# MQ303A_EEPROM_v3_0_-_para_testes.net
KiCad netlist of a schematic drawn in EAGLE
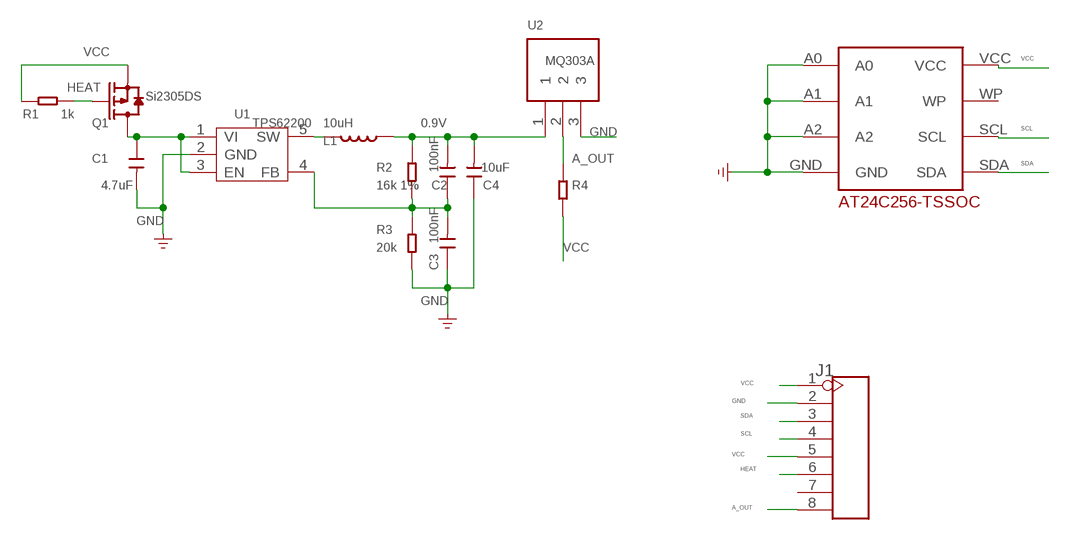
[diagram p0: schematic, sheet 1]

(export (version "E")
  (design (tool "Eeschema 10.0.6"))
  (components
    (comp (ref "C1")
      (value "4.7uF")
      (footprint "eagle-import:C0805")
      (libsource (lib "eagle-import") (part "C-0805"))
    )
    (comp (ref "C2")
      (value "100nF")
      (footprint "eagle-import:C0603")
      (libsource (lib "eagle-import") (part "C-0603"))
    )
    (comp (ref "C3")
      (value "100nF")
      (footprint "eagle-import:C0603")
      (libsource (lib "eagle-import") (part "C-0603"))
    )
    (comp (ref "C4")
      (value "10uF")
      (footprint "eagle-import:C0805")
      (libsource (lib "eagle-import") (part "C-0805"))
    )
    (comp (ref "J1")
      (value "HEADER-8P-2.54")
      (footprint "eagle-import:8P-2.54")
      (libsource (lib "eagle-import") (part "HEADER-8P-2.54"))
    )
    (comp (ref "L1")
      (value "10uH")
      (footprint "eagle-import:PIO73")
      (libsource (lib "eagle-import") (part "L'PIO73'"))
    )
    (comp (ref "Q1")
      (value "Si2305DS")
      (footprint "eagle-import:SOT23")
      (libsource (lib "eagle-import") (part "MOSFET-P'SI2323CDS/SI2305DS{lt}BR{gt}'"))
    )
    (comp (ref "R1")
      (value "1k")
      (footprint "eagle-import:R0603")
      (libsource (lib "eagle-import") (part "R-0603"))
    )
    (comp (ref "R2")
      (value "16k 1%")
      (footprint "eagle-import:R0603")
      (libsource (lib "eagle-import") (part "R-0603"))
    )
    (comp (ref "R3")
      (value "20k")
      (footprint "eagle-import:R0603")
      (libsource (lib "eagle-import") (part "R-0603"))
    )
    (comp (ref "R4")
      (value "R-0603")
      (footprint "eagle-import:R0603")
      (libsource (lib "eagle-import") (part "R-0603"))
    )
    (comp (ref "U$1")
      (value "DECADE-AT24C256-10TI-2.7")
      (footprint "eagle-import:DECADE-AT24CXX")
      (libsource (lib "eagle-import") (part "DECADE-AT24C256-10TI-2.7"))
    )
    (comp (ref "U1")
      (value "TPS62200")
      (footprint "eagle-import:SOT23-5")
      (libsource (lib "eagle-import") (part "TPS62200DBV"))
    )
    (comp (ref "U2")
      (value "MQ303A")
      (footprint "eagle-import:MQ303A")
      (libsource (lib "eagle-import") (part "MQ303A"))
    )
  )
  (nets
    (net (code "1") (name "/0.9V") (class "Default")
      (node (ref "C2") (pin "2") (pinfunction "2_2") (pintype "passive"))
      (node (ref "C4") (pin "2") (pinfunction "2_2") (pintype "passive"))
      (node (ref "L1") (pin "2") (pinfunction "2_2") (pintype "passive"))
      (node (ref "R2") (pin "1") (pinfunction "1_1") (pintype "passive"))
      (node (ref "U2") (pin "1") (pinfunction "1_1") (pintype "bidirectional"))
    )
    (net (code "2") (name "/A_OUT") (class "Default")
      (node (ref "J1") (pin "8") (pinfunction "8_8") (pintype "bidirectional"))
      (node (ref "R4") (pin "1") (pinfunction "1_1") (pintype "passive"))
      (node (ref "U2") (pin "2") (pinfunction "2_2") (pintype "bidirectional"))
    )
    (net (code "3") (name "/HEAT") (class "Default")
      (node (ref "J1") (pin "6") (pinfunction "6_6") (pintype "bidirectional"))
      (node (ref "Q1") (pin "1") (pinfunction "G_1") (pintype "passive"))
      (node (ref "R1") (pin "1") (pinfunction "1_1") (pintype "passive"))
    )
    (net (code "4") (name "/SCL") (class "Default")
      (node (ref "J1") (pin "4") (pinfunction "4_4") (pintype "bidirectional"))
      (node (ref "U$1") (pin "SCL") (pinfunction "SCL_SCL") (pintype "bidirectional"))
    )
    (net (code "5") (name "/SDA") (class "Default")
      (node (ref "J1") (pin "3") (pinfunction "3_3") (pintype "bidirectional"))
      (node (ref "U$1") (pin "SDA") (pinfunction "SDA_SDA") (pintype "bidirectional"))
    )
    (net (code "6") (name "/VCC") (class "Default")
      (node (ref "J1") (pin "1") (pinfunction "1_1") (pintype "bidirectional"))
      (node (ref "J1") (pin "5") (pinfunction "5_5") (pintype "bidirectional"))
      (node (ref "Q1") (pin "2") (pinfunction "S_2") (pintype "passive"))
      (node (ref "R1") (pin "2") (pinfunction "2_2") (pintype "passive"))
      (node (ref "R4") (pin "2") (pinfunction "2_2") (pintype "passive"))
      (node (ref "U$1") (pin "VCC") (pinfunction "VCC_VCC") (pintype "bidirectional"))
    )
    (net (code "7") (name "GND_POWER") (class "Default")
      (node (ref "C1") (pin "2") (pinfunction "2_2") (pintype "passive"))
      (node (ref "C3") (pin "1") (pinfunction "1_1") (pintype "passive"))
      (node (ref "C4") (pin "1") (pinfunction "1_1") (pintype "passive"))
      (node (ref "J1") (pin "2") (pinfunction "2_2") (pintype "bidirectional"))
      (node (ref "R3") (pin "2") (pinfunction "2_2") (pintype "passive"))
      (node (ref "U$1") (pin "A0") (pinfunction "A0_A0") (pintype "bidirectional"))
      (node (ref "U$1") (pin "A1") (pinfunction "A1_A1") (pintype "bidirectional"))
      (node (ref "U$1") (pin "A2") (pinfunction "A2_A2") (pintype "bidirectional"))
      (node (ref "U$1") (pin "GND") (pinfunction "GND_GND") (pintype "bidirectional"))
      (node (ref "U1") (pin "2") (pinfunction "GND_2") (pintype "power_in"))
      (node (ref "U2") (pin "3") (pinfunction "3_3") (pintype "bidirectional"))
    )
    (net (code "8") (name "Net-(Q1-D)") (class "Default")
      (node (ref "C1") (pin "1") (pinfunction "1_1") (pintype "passive"))
      (node (ref "Q1") (pin "3") (pinfunction "D_3") (pintype "passive"))
      (node (ref "U1") (pin "1") (pinfunction "VI_1") (pintype "input"))
      (node (ref "U1") (pin "3") (pinfunction "EN_3") (pintype "input"))
    )
    (net (code "9") (name "Net-(U1-FB)") (class "Default")
      (node (ref "C2") (pin "1") (pinfunction "1_1") (pintype "passive"))
      (node (ref "C3") (pin "2") (pinfunction "2_2") (pintype "passive"))
      (node (ref "R2") (pin "2") (pinfunction "2_2") (pintype "passive"))
      (node (ref "R3") (pin "1") (pinfunction "1_1") (pintype "passive"))
      (node (ref "U1") (pin "4") (pinfunction "FB_4") (pintype "input"))
    )
    (net (code "10") (name "Net-(U1-SW)") (class "Default")
      (node (ref "L1") (pin "1") (pinfunction "1_1") (pintype "passive"))
      (node (ref "U1") (pin "5") (pinfunction "SW_5") (pintype "bidirectional"))
    )
    (net (code "11") (name "unconnected-(J1-Pad7)") (class "Default")
      (node (ref "J1") (pin "7") (pinfunction "7_7") (pintype "bidirectional"))
    )
    (net (code "12") (name "unconnected-(U$1-PadWP)") (class "Default")
      (node (ref "U$1") (pin "WP") (pinfunction "WP_WP") (pintype "bidirectional"))
    )
  )
)
